# cerebellar_V1_1.net
KiCad netlist of a schematic drawn in EAGLE
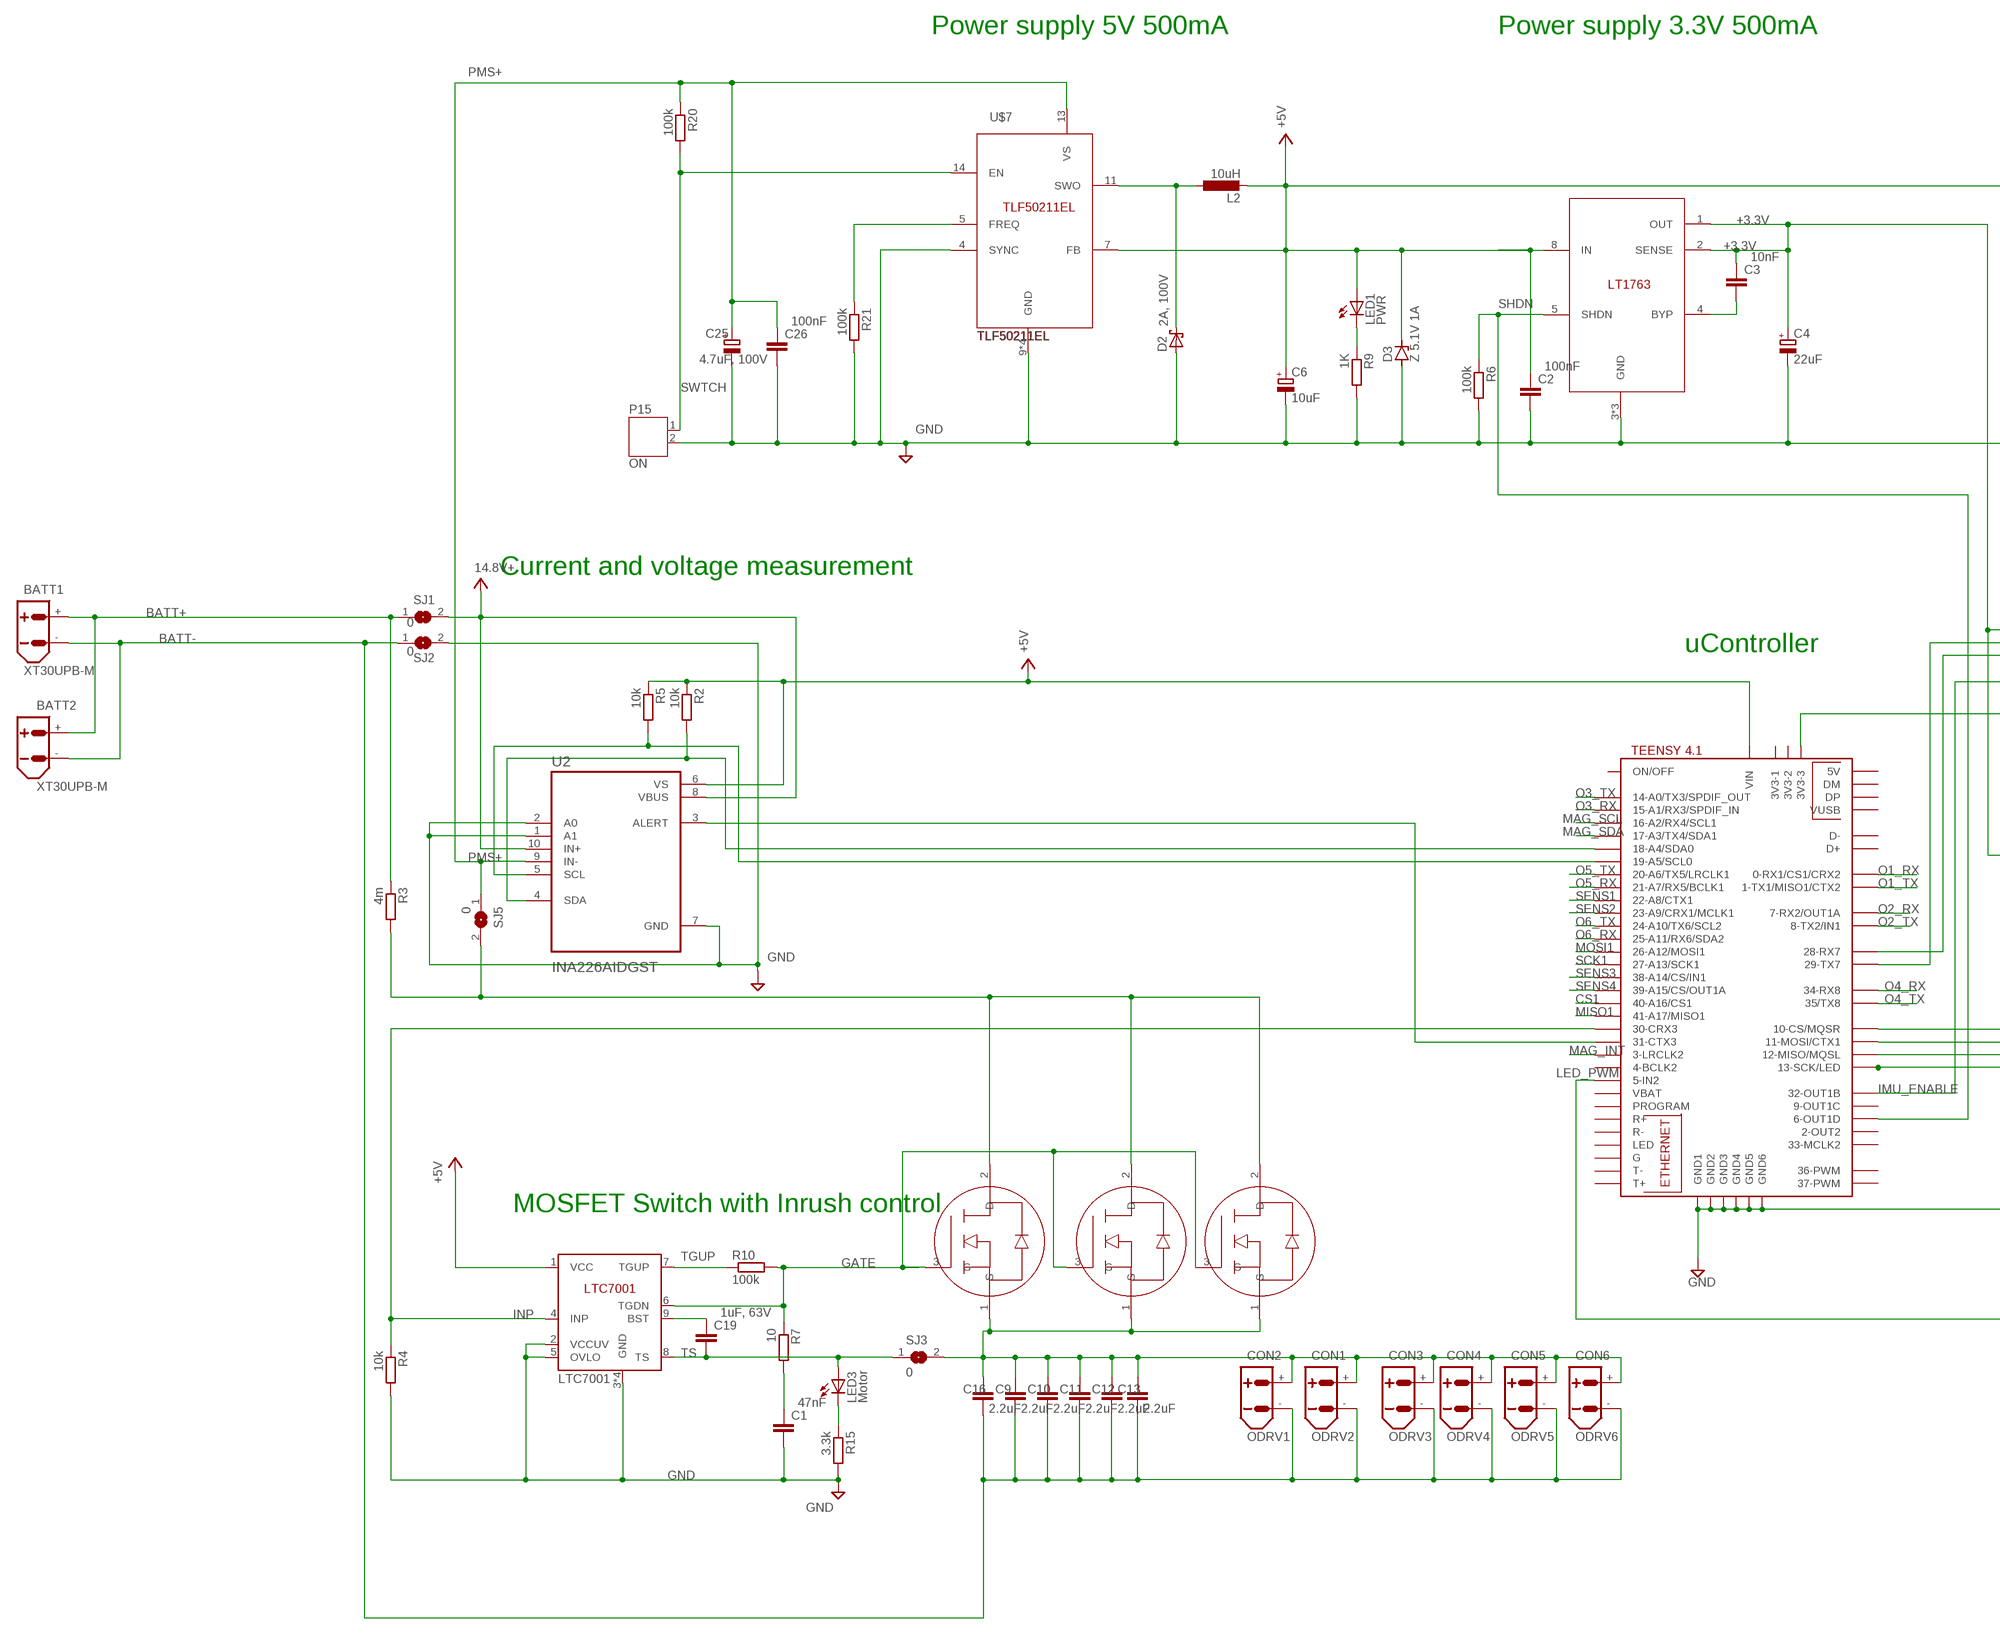
[diagram p0: schematic, sheet 1, part 1 of 2]
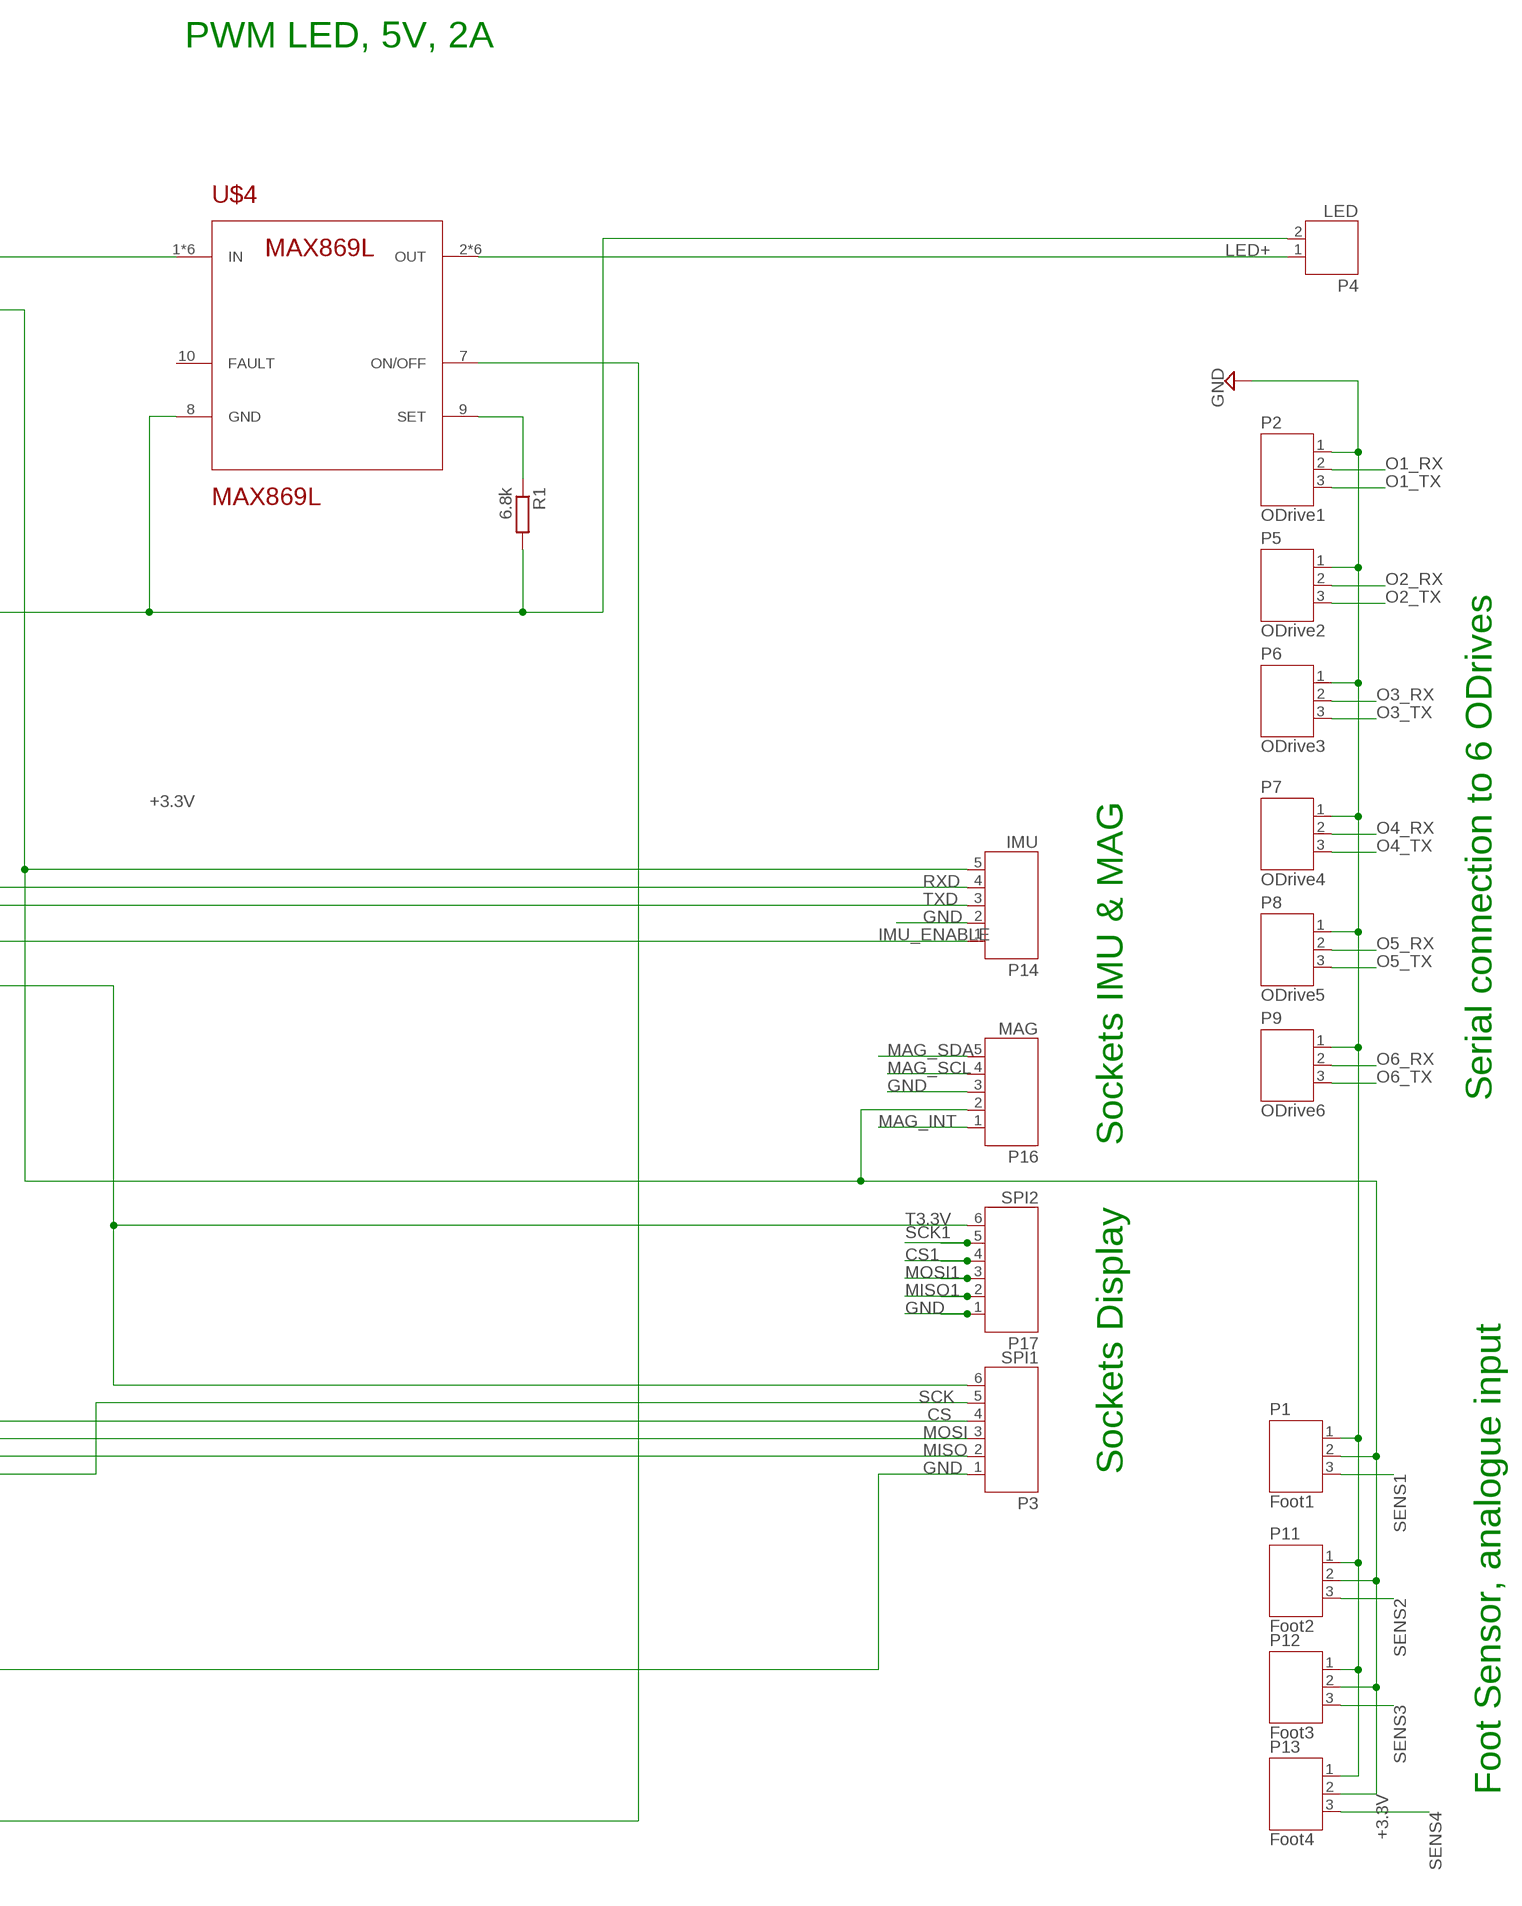
[diagram p1: schematic, sheet 1, part 2 of 2]

(export (version "E")
  (design (tool "Eeschema 10.0.6"))
  (components
    (comp (ref "BATT1")
      (value "XT30UPB-M")
      (footprint "eagle-import:XT30UPB-M")
      (libsource (lib "eagle-import") (part "XT30UPB-M"))
    )
    (comp (ref "BATT2")
      (value "XT30UPB-M")
      (footprint "eagle-import:XT30UPB-M")
      (libsource (lib "eagle-import") (part "XT30UPB-M"))
    )
    (comp (ref "C1")
      (value "47nF")
      (footprint "eagle-import:C050-024X044")
      (libsource (lib "eagle-import") (part "C-EU050-024X044"))
    )
    (comp (ref "C2")
      (value "100nF")
      (footprint "eagle-import:C050-024X044")
      (libsource (lib "eagle-import") (part "C-EU050-024X044"))
    )
    (comp (ref "C3")
      (value "10nF")
      (footprint "eagle-import:C050-024X044")
      (libsource (lib "eagle-import") (part "C-EU050-024X044"))
    )
    (comp (ref "C4")
      (value "22uF")
      (footprint "eagle-import:E2-4")
      (libsource (lib "eagle-import") (part "CPOL-EUE2-4"))
    )
    (comp (ref "C6")
      (value "10uF")
      (footprint "eagle-import:E2-4")
      (libsource (lib "eagle-import") (part "CPOL-EUE2-4"))
    )
    (comp (ref "C9")
      (value "2.2uF")
      (footprint "eagle-import:C050-024X044")
      (libsource (lib "eagle-import") (part "C-EU050-024X044"))
    )
    (comp (ref "C10")
      (value "2.2uF")
      (footprint "eagle-import:C050-024X044")
      (libsource (lib "eagle-import") (part "C-EU050-024X044"))
    )
    (comp (ref "C11")
      (value "2.2uF")
      (footprint "eagle-import:C050-024X044")
      (libsource (lib "eagle-import") (part "C-EU050-024X044"))
    )
    (comp (ref "C12")
      (value "2.2uF")
      (footprint "eagle-import:C050-024X044")
      (libsource (lib "eagle-import") (part "C-EU050-024X044"))
    )
    (comp (ref "C13")
      (value "2.2uF")
      (footprint "eagle-import:C050-024X044")
      (libsource (lib "eagle-import") (part "C-EU050-024X044"))
    )
    (comp (ref "C16")
      (value "2.2uF")
      (footprint "eagle-import:C050-024X044")
      (libsource (lib "eagle-import") (part "C-EU050-024X044"))
    )
    (comp (ref "C19")
      (value "1uF, 63V")
      (footprint "eagle-import:C050-024X044")
      (libsource (lib "eagle-import") (part "C-EU050-024X044"))
    )
    (comp (ref "C25")
      (value "4.7uF, 100V")
      (footprint "eagle-import:E2-4")
      (libsource (lib "eagle-import") (part "CPOL-EUE2-4"))
    )
    (comp (ref "C26")
      (value "100nF")
      (footprint "eagle-import:C050-024X044")
      (libsource (lib "eagle-import") (part "C-EU050-024X044"))
    )
    (comp (ref "CON1")
      (value "ODRV2")
      (footprint "eagle-import:XT30UPB-F")
      (libsource (lib "eagle-import") (part "XT30UPB-F"))
    )
    (comp (ref "CON2")
      (value "ODRV1")
      (footprint "eagle-import:XT30UPB-F")
      (libsource (lib "eagle-import") (part "XT30UPB-F"))
    )
    (comp (ref "CON3")
      (value "ODRV3")
      (footprint "eagle-import:XT30UPB-F")
      (libsource (lib "eagle-import") (part "XT30UPB-F"))
    )
    (comp (ref "CON4")
      (value "ODRV4")
      (footprint "eagle-import:XT30UPB-F")
      (libsource (lib "eagle-import") (part "XT30UPB-F"))
    )
    (comp (ref "CON5")
      (value "ODRV5")
      (footprint "eagle-import:XT30UPB-F")
      (libsource (lib "eagle-import") (part "XT30UPB-F"))
    )
    (comp (ref "CON6")
      (value "ODRV6")
      (footprint "eagle-import:XT30UPB-F")
      (libsource (lib "eagle-import") (part "XT30UPB-F"))
    )
    (comp (ref "D2")
      (value "2A, 100V")
      (footprint "eagle-import:DO41-10")
      (libsource (lib "eagle-import") (part "SCHOTTKY-DIODEDO41"))
    )
    (comp (ref "D3")
      (value "Z 5.1V 1A")
      (footprint "eagle-import:DO41Z10")
      (libsource (lib "eagle-import") (part "ZENER-DIODEDO41Z10"))
    )
    (comp (ref "IC3")
      (value "LTC7001")
      (footprint "eagle-import:MSOP10")
      (fields (field (name "MPN") "AD7992BRMZ-0"))
      (libsource (lib "eagle-import") (part "LTC7001"))
    )
    (comp (ref "L2")
      (value "10uH")
      (footprint "eagle-import:IRF-3")
      (libsource (lib "eagle-import") (part "L-EUIRF-3"))
    )
    (comp (ref "LED1")
      (value "PWR")
      (footprint "eagle-import:LED3MM")
      (libsource (lib "eagle-import") (part "LED3MM"))
    )
    (comp (ref "LED3")
      (value "Motor")
      (footprint "eagle-import:LED3MM")
      (libsource (lib "eagle-import") (part "LED3MM"))
    )
    (comp (ref "P1")
      (value "Foot1")
      (footprint "eagle-import:JST-PH3")
      (libsource (lib "eagle-import") (part "JST-PH3"))
    )
    (comp (ref "P2")
      (value "ODrive1")
      (footprint "eagle-import:JST-PH3")
      (libsource (lib "eagle-import") (part "JST-PH3"))
    )
    (comp (ref "P3")
      (value "SPI1")
      (footprint "eagle-import:JST-PH6")
      (libsource (lib "eagle-import") (part "JST-PH6"))
    )
    (comp (ref "P4")
      (value "LED")
      (footprint "eagle-import:JST-PH2")
      (libsource (lib "eagle-import") (part "JST-PH2"))
    )
    (comp (ref "P5")
      (value "ODrive2")
      (footprint "eagle-import:JST-PH3")
      (libsource (lib "eagle-import") (part "JST-PH3"))
    )
    (comp (ref "P6")
      (value "ODrive3")
      (footprint "eagle-import:JST-PH3")
      (libsource (lib "eagle-import") (part "JST-PH3"))
    )
    (comp (ref "P7")
      (value "ODrive4")
      (footprint "eagle-import:JST-PH3")
      (libsource (lib "eagle-import") (part "JST-PH3"))
    )
    (comp (ref "P8")
      (value "ODrive5")
      (footprint "eagle-import:JST-PH3")
      (libsource (lib "eagle-import") (part "JST-PH3"))
    )
    (comp (ref "P9")
      (value "ODrive6")
      (footprint "eagle-import:JST-PH3")
      (libsource (lib "eagle-import") (part "JST-PH3"))
    )
    (comp (ref "P11")
      (value "Foot2")
      (footprint "eagle-import:JST-PH3")
      (libsource (lib "eagle-import") (part "JST-PH3"))
    )
    (comp (ref "P12")
      (value "Foot3")
      (footprint "eagle-import:JST-PH3")
      (libsource (lib "eagle-import") (part "JST-PH3"))
    )
    (comp (ref "P13")
      (value "Foot4")
      (footprint "eagle-import:JST-PH3")
      (libsource (lib "eagle-import") (part "JST-PH3"))
    )
    (comp (ref "P14")
      (value "IMU")
      (footprint "eagle-import:JST-PH5")
      (libsource (lib "eagle-import") (part "JST-PH5"))
    )
    (comp (ref "P15")
      (value "ON")
      (footprint "eagle-import:JST-PH2")
      (libsource (lib "eagle-import") (part "JST-PH2"))
    )
    (comp (ref "P16")
      (value "MAG")
      (footprint "eagle-import:JST-PH5")
      (libsource (lib "eagle-import") (part "JST-PH5"))
    )
    (comp (ref "P17")
      (value "SPI2")
      (footprint "eagle-import:JST-PH6")
      (libsource (lib "eagle-import") (part "JST-PH6"))
    )
    (comp (ref "R1")
      (value "6.8k")
      (footprint "eagle-import:0204_7")
      (libsource (lib "eagle-import") (part "R-EU_0204/7"))
    )
    (comp (ref "R2")
      (value "10k")
      (footprint "eagle-import:0204_7")
      (libsource (lib "eagle-import") (part "R-EU_0204/7"))
    )
    (comp (ref "R3")
      (value "4m")
      (footprint "eagle-import:R2512")
      (libsource (lib "eagle-import") (part "R-EU_R2512"))
    )
    (comp (ref "R4")
      (value "10k")
      (footprint "eagle-import:0204_7")
      (libsource (lib "eagle-import") (part "R-EU_0204/7"))
    )
    (comp (ref "R5")
      (value "10k")
      (footprint "eagle-import:0204_7")
      (libsource (lib "eagle-import") (part "R-EU_0204/7"))
    )
    (comp (ref "R6")
      (value "100k")
      (footprint "eagle-import:0204_7")
      (libsource (lib "eagle-import") (part "R-EU_0204/7"))
    )
    (comp (ref "R7")
      (value "10")
      (footprint "eagle-import:0204_7")
      (libsource (lib "eagle-import") (part "R-EU_0204/7"))
    )
    (comp (ref "R9")
      (value "1K")
      (footprint "eagle-import:0204_7")
      (libsource (lib "eagle-import") (part "R-EU_0204/7"))
    )
    (comp (ref "R10")
      (value "100k")
      (footprint "eagle-import:0204_7")
      (libsource (lib "eagle-import") (part "R-EU_0204/7"))
    )
    (comp (ref "R15")
      (value "3.3k")
      (footprint "eagle-import:0204_7")
      (libsource (lib "eagle-import") (part "R-EU_0204/7"))
    )
    (comp (ref "R20")
      (value "100k")
      (footprint "eagle-import:0204_7")
      (libsource (lib "eagle-import") (part "R-EU_0204/7"))
    )
    (comp (ref "R21")
      (value "100k")
      (footprint "eagle-import:0204_7")
      (libsource (lib "eagle-import") (part "R-EU_0204/7"))
    )
    (comp (ref "SJ1") (value "0") (footprint "eagle-import:SJ") (libsource (lib "eagle-import") (part "SJ")))
    (comp (ref "SJ2") (value "0") (footprint "eagle-import:SJ") (libsource (lib "eagle-import") (part "SJ")))
    (comp (ref "SJ3") (value "0") (footprint "eagle-import:SJ") (libsource (lib "eagle-import") (part "SJ")))
    (comp (ref "SJ5") (value "0") (footprint "eagle-import:SJ") (libsource (lib "eagle-import") (part "SJ")))
    (comp (ref "U$1")
      (value "TEENSY41")
      (footprint "eagle-import:TEENSY41")
      (libsource (lib "eagle-import") (part "TEENSY41"))
    )
    (comp (ref "U$2")
      (value "IRF2804-BACK")
      (footprint "eagle-import:TO-220H-BACK")
      (libsource (lib "eagle-import") (part "IRF2804-BACK"))
    )
    (comp (ref "U$3")
      (value "IRF2804-BACK")
      (footprint "eagle-import:TO-220H-BACK")
      (libsource (lib "eagle-import") (part "IRF2804-BACK"))
    )
    (comp (ref "U$4")
      (value "MAX869L")
      (footprint "eagle-import:TSSOP-16")
      (libsource (lib "eagle-import") (part "MAX769L"))
    )
    (comp (ref "U$5")
      (value "IRF2804-BACK")
      (footprint "eagle-import:TO-220H-BACK")
      (libsource (lib "eagle-import") (part "IRF2804-BACK"))
    )
    (comp (ref "U$7")
      (value "TLF50211EL")
      (footprint "eagle-import:TSSOP-14")
      (libsource (lib "eagle-import") (part "TLF50211EL"))
    )
    (comp (ref "U$8")
      (value "LT1763")
      (footprint "eagle-import:SO08")
      (libsource (lib "eagle-import") (part "LT1763"))
    )
    (comp (ref "U2")
      (value "INA226AIDGST")
      (footprint "eagle-import:SOP50P490X110-10N")
      (fields (field (name "MF") "Texas Instruments"))
      (libsource (lib "eagle-import") (part "INA226AIDGST"))
    )
  )
  (nets
    (net (code "1") (name "+5V") (class "Default")
      (node (ref "C2") (pin "1") (pinfunction "1_1") (pintype "passive"))
      (node (ref "C6") (pin "+") (pinfunction "+_+") (pintype "passive"))
      (node (ref "D3") (pin "C") (pinfunction "C_C") (pintype "passive"))
      (node (ref "IC3") (pin "1") (pinfunction "VCC_1") (pintype "power_in"))
      (node (ref "L2") (pin "2") (pinfunction "2_2") (pintype "passive"))
      (node (ref "LED1") (pin "A") (pinfunction "A_A") (pintype "passive"))
      (node (ref "R2") (pin "1") (pinfunction "1_1") (pintype "passive"))
      (node (ref "R5") (pin "1") (pinfunction "1_1") (pintype "passive"))
      (node (ref "U$1") (pin "VIN") (pinfunction "VIN_VIN") (pintype "bidirectional"))
      (node (ref "U$4") (pin "1") (pinfunction "IN_1") (pintype "bidirectional"))
      (node (ref "U$4") (pin "12") (pinfunction "IN_12") (pintype "bidirectional"))
      (node (ref "U$4") (pin "13") (pinfunction "IN_13") (pintype "bidirectional"))
      (node (ref "U$4") (pin "16") (pinfunction "IN_16") (pintype "bidirectional"))
      (node (ref "U$4") (pin "4") (pinfunction "IN_4") (pintype "bidirectional"))
      (node (ref "U$4") (pin "5") (pinfunction "IN_5") (pintype "bidirectional"))
      (node (ref "U$7") (pin "7") (pinfunction "FB_7") (pintype "bidirectional"))
      (node (ref "U$8") (pin "8") (pinfunction "IN_8") (pintype "input"))
      (node (ref "U2") (pin "6") (pinfunction "VS_6") (pintype "power_in"))
    )
    (net (code "2") (name "/+3.3V") (class "Default")
      (node (ref "C3") (pin "1") (pinfunction "1_1") (pintype "passive"))
      (node (ref "C4") (pin "+") (pinfunction "+_+") (pintype "passive"))
      (node (ref "P1") (pin "2") (pinfunction "2_2") (pintype "passive"))
      (node (ref "P11") (pin "2") (pinfunction "2_2") (pintype "passive"))
      (node (ref "P12") (pin "2") (pinfunction "2_2") (pintype "passive"))
      (node (ref "P13") (pin "2") (pinfunction "2_2") (pintype "passive"))
      (node (ref "P14") (pin "5") (pinfunction "5_5") (pintype "passive"))
      (node (ref "P16") (pin "2") (pinfunction "2_2") (pintype "passive"))
      (node (ref "U$8") (pin "1") (pinfunction "OUT_1") (pintype "output"))
      (node (ref "U$8") (pin "2") (pinfunction "SENSE_2") (pintype "input"))
    )
    (net (code "3") (name "/BATT+") (class "Default")
      (node (ref "BATT1") (pin "+") (pinfunction "+_+") (pintype "power_in"))
      (node (ref "BATT2") (pin "+") (pinfunction "+_+") (pintype "power_in"))
      (node (ref "R3") (pin "1") (pinfunction "1_1") (pintype "passive"))
      (node (ref "SJ1") (pin "1") (pinfunction "1_1") (pintype "passive"))
    )
    (net (code "4") (name "/BATT-") (class "Default")
      (node (ref "BATT1") (pin "-") (pinfunction "-_-") (pintype "power_in"))
      (node (ref "BATT2") (pin "-") (pinfunction "-_-") (pintype "power_in"))
      (node (ref "C10") (pin "2") (pinfunction "2_2") (pintype "passive"))
      (node (ref "C11") (pin "2") (pinfunction "2_2") (pintype "passive"))
      (node (ref "C12") (pin "2") (pinfunction "2_2") (pintype "passive"))
      (node (ref "C13") (pin "2") (pinfunction "2_2") (pintype "passive"))
      (node (ref "C16") (pin "2") (pinfunction "2_2") (pintype "passive"))
      (node (ref "C9") (pin "2") (pinfunction "2_2") (pintype "passive"))
      (node (ref "CON1") (pin "-") (pinfunction "-_-") (pintype "power_in"))
      (node (ref "CON2") (pin "-") (pinfunction "-_-") (pintype "power_in"))
      (node (ref "CON3") (pin "-") (pinfunction "-_-") (pintype "power_in"))
      (node (ref "CON4") (pin "-") (pinfunction "-_-") (pintype "power_in"))
      (node (ref "CON5") (pin "-") (pinfunction "-_-") (pintype "power_in"))
      (node (ref "CON6") (pin "-") (pinfunction "-_-") (pintype "power_in"))
      (node (ref "SJ2") (pin "1") (pinfunction "1_1") (pintype "passive"))
    )
    (net (code "5") (name "/CS") (class "Default")
      (node (ref "P3") (pin "4") (pinfunction "4_4") (pintype "passive"))
      (node (ref "U$1") (pin "10-CS\\MQSR") (pinfunction "10-CS/MQSR_10-CS\\MQSR") (pintype "bidirectional"))
    )
    (net (code "6") (name "/CS1") (class "Default")
      (node (ref "P17") (pin "4") (pinfunction "4_4") (pintype "passive"))
      (node (ref "U$1") (pin "40-A16/CS1") (pinfunction "40-A16/CS1_40-A16/CS1") (pintype "bidirectional"))
    )
    (net (code "7") (name "/GATE") (class "Default")
      (node (ref "IC3") (pin "6") (pinfunction "TGDN_6") (pintype "output"))
      (node (ref "R10") (pin "2") (pinfunction "2_2") (pintype "passive"))
      (node (ref "R7") (pin "1") (pinfunction "1_1") (pintype "passive"))
      (node (ref "U$2") (pin "3") (pinfunction "G_3") (pintype "bidirectional"))
      (node (ref "U$3") (pin "3") (pinfunction "G_3") (pintype "bidirectional"))
      (node (ref "U$5") (pin "3") (pinfunction "G_3") (pintype "bidirectional"))
    )
    (net (code "8") (name "/IMU_ENABLE") (class "Default")
      (node (ref "P14") (pin "1") (pinfunction "1_1") (pintype "passive"))
      (node (ref "U$1") (pin "32-OUT1B") (pinfunction "32-OUT1B_32-OUT1B") (pintype "bidirectional"))
    )
    (net (code "9") (name "/INP") (class "Default")
      (node (ref "IC3") (pin "4") (pinfunction "INP_4") (pintype "input"))
      (node (ref "R4") (pin "1") (pinfunction "1_1") (pintype "passive"))
      (node (ref "U$1") (pin "30-CRX3") (pinfunction "30-CRX3_30-CRX3") (pintype "bidirectional"))
    )
    (net (code "10") (name "/LED+") (class "Default")
      (node (ref "P4") (pin "1") (pinfunction "1_1") (pintype "passive"))
      (node (ref "U$4") (pin "11") (pinfunction "OUT_11") (pintype "bidirectional"))
      (node (ref "U$4") (pin "14") (pinfunction "OUT_14") (pintype "bidirectional"))
      (node (ref "U$4") (pin "15") (pinfunction "OUT_15") (pintype "bidirectional"))
      (node (ref "U$4") (pin "2") (pinfunction "OUT_2") (pintype "bidirectional"))
      (node (ref "U$4") (pin "3") (pinfunction "OUT_3") (pintype "bidirectional"))
      (node (ref "U$4") (pin "6") (pinfunction "OUT_6") (pintype "bidirectional"))
    )
    (net (code "11") (name "/LED_PWM") (class "Default")
      (node (ref "U$1") (pin "5-IN2") (pinfunction "5-IN2_5-IN2") (pintype "bidirectional"))
      (node (ref "U$4") (pin "7") (pinfunction "ON/OFF_7") (pintype "bidirectional"))
    )
    (net (code "12") (name "/MAG_INT") (class "Default")
      (node (ref "P16") (pin "1") (pinfunction "1_1") (pintype "passive"))
      (node (ref "U$1") (pin "3-LRCLK2") (pinfunction "3-LRCLK2_3-LRCLK2") (pintype "bidirectional"))
    )
    (net (code "13") (name "/MAG_SCL") (class "Default")
      (node (ref "P16") (pin "4") (pinfunction "4_4") (pintype "passive"))
      (node (ref "U$1") (pin "16-A2/RX4/SCL1") (pinfunction "16-A2/RX4/SCL1_16-A2/RX4/SCL1") (pintype "bidirectional"))
    )
    (net (code "14") (name "/MAG_SDA") (class "Default")
      (node (ref "P16") (pin "5") (pinfunction "5_5") (pintype "passive"))
      (node (ref "U$1") (pin "17-A3/TX4/SDA1") (pinfunction "17-A3/TX4/SDA1_17-A3/TX4/SDA1") (pintype "bidirectional"))
    )
    (net (code "15") (name "/MISO") (class "Default")
      (node (ref "P3") (pin "2") (pinfunction "2_2") (pintype "passive"))
      (node (ref "U$1") (pin "12-MISO/MQSL") (pinfunction "12-MISO/MQSL_12-MISO/MQSL") (pintype "bidirectional"))
    )
    (net (code "16") (name "/MISO1") (class "Default")
      (node (ref "P17") (pin "2") (pinfunction "2_2") (pintype "passive"))
      (node (ref "U$1") (pin "41-A17/MISO1") (pinfunction "41-A17/MISO1_41-A17/MISO1") (pintype "bidirectional"))
    )
    (net (code "17") (name "/MOSI") (class "Default")
      (node (ref "P3") (pin "3") (pinfunction "3_3") (pintype "passive"))
      (node (ref "U$1") (pin "11-MOSI/CTX1") (pinfunction "11-MOSI/CTX1_11-MOSI/CTX1") (pintype "bidirectional"))
    )
    (net (code "18") (name "/MOSI1") (class "Default")
      (node (ref "P17") (pin "3") (pinfunction "3_3") (pintype "passive"))
      (node (ref "U$1") (pin "26-A12/MOSI1") (pinfunction "26-A12/MOSI1_26-A12/MOSI1") (pintype "bidirectional"))
    )
    (net (code "19") (name "/O1_RX") (class "Default")
      (node (ref "P2") (pin "2") (pinfunction "2_2") (pintype "passive"))
      (node (ref "U$1") (pin "0-RX1/CS1/CRX2") (pinfunction "0-RX1/CS1/CRX2_0-RX1/CS1/CRX2") (pintype "bidirectional"))
    )
    (net (code "20") (name "/O1_TX") (class "Default")
      (node (ref "P2") (pin "3") (pinfunction "3_3") (pintype "passive"))
      (node (ref "U$1") (pin "1-TX1/MISO1/CTX2") (pinfunction "1-TX1/MISO1/CTX2_1-TX1/MISO1/CTX2") (pintype "bidirectional"))
    )
    (net (code "21") (name "/O2_RX") (class "Default")
      (node (ref "P5") (pin "2") (pinfunction "2_2") (pintype "passive"))
      (node (ref "U$1") (pin "7-RX2/OUT1A") (pinfunction "7-RX2/OUT1A_7-RX2/OUT1A") (pintype "bidirectional"))
    )
    (net (code "22") (name "/O2_TX") (class "Default")
      (node (ref "P5") (pin "3") (pinfunction "3_3") (pintype "passive"))
      (node (ref "U$1") (pin "8-TX2/IN1") (pinfunction "8-TX2/IN1_8-TX2/IN1") (pintype "bidirectional"))
    )
    (net (code "23") (name "/O3_RX") (class "Default")
      (node (ref "P6") (pin "2") (pinfunction "2_2") (pintype "passive"))
      (node (ref "U$1") (pin "15-A1/RX3/SPDIF_IN") (pinfunction "15-A1/RX3/SPDIF_IN_15-A1/RX3/SPDIF_IN") (pintype "bidirectional"))
    )
    (net (code "24") (name "/O3_TX") (class "Default")
      (node (ref "P6") (pin "3") (pinfunction "3_3") (pintype "passive"))
      (node (ref "U$1") (pin "14-A0/TX3/SPDIF_OUT") (pinfunction "14-A0/TX3/SPDIF_OUT_14-A0/TX3/SPDIF_OUT") (pintype "bidirectional"))
    )
    (net (code "25") (name "/O4_RX") (class "Default")
      (node (ref "P7") (pin "2") (pinfunction "2_2") (pintype "passive"))
      (node (ref "U$1") (pin "34-RX8") (pinfunction "34-RX8_34-RX8") (pintype "bidirectional"))
    )
    (net (code "26") (name "/O4_TX") (class "Default")
      (node (ref "P7") (pin "3") (pinfunction "3_3") (pintype "passive"))
      (node (ref "U$1") (pin "35-TX8") (pinfunction "35/TX8_35-TX8") (pintype "bidirectional"))
    )
    (net (code "27") (name "/O5_RX") (class "Default")
      (node (ref "P8") (pin "2") (pinfunction "2_2") (pintype "passive"))
      (node (ref "U$1") (pin "21-A7/RX5/BCLK1") (pinfunction "21-A7/RX5/BCLK1_21-A7/RX5/BCLK1") (pintype "bidirectional"))
    )
    (net (code "28") (name "/O5_TX") (class "Default")
      (node (ref "P8") (pin "3") (pinfunction "3_3") (pintype "passive"))
      (node (ref "U$1") (pin "20-A6/TX5/LRCLK1") (pinfunction "20-A6/TX5/LRCLK1_20-A6/TX5/LRCLK1") (pintype "bidirectional"))
    )
    (net (code "29") (name "/O6_RX") (class "Default")
      (node (ref "P9") (pin "2") (pinfunction "2_2") (pintype "passive"))
      (node (ref "U$1") (pin "25-A11/RX6/SDA2") (pinfunction "25-A11/RX6/SDA2_25-A11/RX6/SDA2") (pintype "bidirectional"))
    )
    (net (code "30") (name "/O6_TX") (class "Default")
      (node (ref "P9") (pin "3") (pinfunction "3_3") (pintype "passive"))
      (node (ref "U$1") (pin "24-A10/TX6/SCL2") (pinfunction "24-A10/TX6/SCL2_24-A10/TX6/SCL2") (pintype "bidirectional"))
    )
    (net (code "31") (name "/PMS+") (class "Default")
      (node (ref "C25") (pin "+") (pinfunction "+_+") (pintype "passive"))
      (node (ref "C26") (pin "1") (pinfunction "1_1") (pintype "passive"))
      (node (ref "R20") (pin "1") (pinfunction "1_1") (pintype "passive"))
      (node (ref "SJ5") (pin "1") (pinfunction "1_1") (pintype "passive"))
      (node (ref "U$7") (pin "13") (pinfunction "VS_13") (pintype "bidirectional"))
      (node (ref "U2") (pin "9") (pinfunction "IN-_9") (pintype "input"))
    )
    (net (code "32") (name "/RXD") (class "Default")
      (node (ref "P14") (pin "4") (pinfunction "4_4") (pintype "passive"))
      (node (ref "U$1") (pin "29-TX7") (pinfunction "29-TX7_29-TX7") (pintype "bidirectional"))
    )
    (net (code "33") (name "/SCK") (class "Default")
      (node (ref "P3") (pin "5") (pinfunction "5_5") (pintype "passive"))
      (node (ref "U$1") (pin "13-SCK/LED") (pinfunction "13-SCK/LED_13-SCK/LED") (pintype "bidirectional"))
    )
    (net (code "34") (name "/SCK1") (class "Default")
      (node (ref "P17") (pin "5") (pinfunction "5_5") (pintype "passive"))
      (node (ref "U$1") (pin "27-A13/SCK1") (pinfunction "27-A13/SCK1_27-A13/SCK1") (pintype "bidirectional"))
    )
    (net (code "35") (name "/SENS1") (class "Default")
      (node (ref "P1") (pin "3") (pinfunction "3_3") (pintype "passive"))
      (node (ref "U$1") (pin "22-A8/CTX1") (pinfunction "22-A8/CTX1_22-A8/CTX1") (pintype "bidirectional"))
    )
    (net (code "36") (name "/SENS2") (class "Default")
      (node (ref "P11") (pin "3") (pinfunction "3_3") (pintype "passive"))
      (node (ref "U$1") (pin "23-A9/CRX1/MCLK1") (pinfunction "23-A9/CRX1/MCLK1_23-A9/CRX1/MCLK1") (pintype "bidirectional"))
    )
    (net (code "37") (name "/SENS3") (class "Default")
      (node (ref "P12") (pin "3") (pinfunction "3_3") (pintype "passive"))
      (node (ref "U$1") (pin "38-A14/CS/IN1") (pinfunction "38-A14/CS/IN1_38-A14/CS/IN1") (pintype "bidirectional"))
    )
    (net (code "38") (name "/SENS4") (class "Default")
      (node (ref "P13") (pin "3") (pinfunction "3_3") (pintype "passive"))
      (node (ref "U$1") (pin "39-A15/CS/OUT1A") (pinfunction "39-A15/CS/OUT1A_39-A15/CS/OUT1A") (pintype "bidirectional"))
    )
    (net (code "39") (name "/SHDN") (class "Default")
      (node (ref "R6") (pin "1") (pinfunction "1_1") (pintype "passive"))
      (node (ref "U$1") (pin "6-OUT1D") (pinfunction "6-OUT1D_6-OUT1D") (pintype "bidirectional"))
      (node (ref "U$8") (pin "5") (pinfunction "SHDN_5") (pintype "bidirectional"))
    )
    (net (code "40") (name "/SWTCH") (class "Default")
      (node (ref "P15") (pin "1") (pinfunction "1_1") (pintype "passive"))
      (node (ref "R20") (pin "2") (pinfunction "2_2") (pintype "passive"))
      (node (ref "U$7") (pin "14") (pinfunction "EN_14") (pintype "bidirectional"))
    )
    (net (code "41") (name "/T3.3V") (class "Default")
      (node (ref "P17") (pin "6") (pinfunction "6_6") (pintype "passive"))
      (node (ref "P3") (pin "6") (pinfunction "6_6") (pintype "passive"))
      (node (ref "U$1") (pin "3V3-3") (pinfunction "3V3-3_3V3-3") (pintype "bidirectional"))
    )
    (net (code "42") (name "/TGUP") (class "Default")
      (node (ref "IC3") (pin "7") (pinfunction "TGUP_7") (pintype "input"))
      (node (ref "R10") (pin "1") (pinfunction "1_1") (pintype "passive"))
    )
    (net (code "43") (name "/TS") (class "Default")
      (node (ref "C19") (pin "2") (pinfunction "2_2") (pintype "passive"))
      (node (ref "IC3") (pin "8") (pinfunction "TS_8") (pintype "bidirectional"))
      (node (ref "LED3") (pin "A") (pinfunction "A_A") (pintype "passive"))
      (node (ref "SJ3") (pin "1") (pinfunction "1_1") (pintype "passive"))
    )
    (net (code "44") (name "/TXD") (class "Default")
      (node (ref "P14") (pin "3") (pinfunction "3_3") (pintype "passive"))
      (node (ref "U$1") (pin "28-RX7") (pinfunction "28-RX7_28-RX7") (pintype "bidirectional"))
    )
    (net (code "45") (name "14.8V+") (class "Default")
      (node (ref "SJ1") (pin "2") (pinfunction "2_2") (pintype "passive"))
      (node (ref "U2") (pin "10") (pinfunction "IN+_10") (pintype "input"))
      (node (ref "U2") (pin "8") (pinfunction "VBUS_8") (pintype "power_in"))
    )
    (net (code "46") (name "GND") (class "Default")
      (node (ref "C1") (pin "2") (pinfunction "2_2") (pintype "passive"))
      (node (ref "C2") (pin "2") (pinfunction "2_2") (pintype "passive"))
      (node (ref "C25") (pin "-") (pinfunction "-_-") (pintype "passive"))
      (node (ref "C26") (pin "2") (pinfunction "2_2") (pintype "passive"))
      (node (ref "C4") (pin "-") (pinfunction "-_-") (pintype "passive"))
      (node (ref "C6") (pin "-") (pinfunction "-_-") (pintype "passive"))
      (node (ref "D2") (pin "A") (pinfunction "A_A") (pintype "passive"))
      (node (ref "D3") (pin "A") (pinfunction "A_A") (pintype "passive"))
      (node (ref "IC3") (pin "10") (pinfunction "GND_10") (pintype "power_in"))
      (node (ref "IC3") (pin "11") (pinfunction "GND_11") (pintype "power_in"))
      (node (ref "IC3") (pin "12") (pinfunction "GND_12") (pintype "power_in"))
      (node (ref "IC3") (pin "2") (pinfunction "VCCUV_2") (pintype "input"))
      (node (ref "IC3") (pin "3") (pinfunction "GND_3") (pintype "power_in"))
      (node (ref "IC3") (pin "5") (pinfunction "OVLO_5") (pintype "input"))
      (node (ref "P1") (pin "1") (pinfunction "1_1") (pintype "passive"))
      (node (ref "P11") (pin "1") (pinfunction "1_1") (pintype "passive"))
      (node (ref "P12") (pin "1") (pinfunction "1_1") (pintype "passive"))
      (node (ref "P13") (pin "1") (pinfunction "1_1") (pintype "passive"))
      (node (ref "P14") (pin "2") (pinfunction "2_2") (pintype "passive"))
      (node (ref "P15") (pin "2") (pinfunction "2_2") (pintype "passive"))
      (node (ref "P16") (pin "3") (pinfunction "3_3") (pintype "passive"))
      (node (ref "P17") (pin "1") (pinfunction "1_1") (pintype "passive"))
      (node (ref "P2") (pin "1") (pinfunction "1_1") (pintype "passive"))
      (node (ref "P3") (pin "1") (pinfunction "1_1") (pintype "passive"))
      (node (ref "P4") (pin "2") (pinfunction "2_2") (pintype "passive"))
      (node (ref "P5") (pin "1") (pinfunction "1_1") (pintype "passive"))
      (node (ref "P6") (pin "1") (pinfunction "1_1") (pintype "passive"))
      (node (ref "P7") (pin "1") (pinfunction "1_1") (pintype "passive"))
      (node (ref "P8") (pin "1") (pinfunction "1_1") (pintype "passive"))
      (node (ref "P9") (pin "1") (pinfunction "1_1") (pintype "passive"))
      (node (ref "R1") (pin "2") (pinfunction "2_2") (pintype "passive"))
      (node (ref "R15") (pin "2") (pinfunction "2_2") (pintype "passive"))
      (node (ref "R21") (pin "2") (pinfunction "2_2") (pintype "passive"))
      (node (ref "R4") (pin "2") (pinfunction "2_2") (pintype "passive"))
      (node (ref "R6") (pin "2") (pinfunction "2_2") (pintype "passive"))
      (node (ref "R9") (pin "2") (pinfunction "2_2") (pintype "passive"))
      (node (ref "SJ2") (pin "2") (pinfunction "2_2") (pintype "passive"))
      (node (ref "U$1") (pin "GND1") (pinfunction "GND1_GND1") (pintype "bidirectional"))
      (node (ref "U$1") (pin "GND2") (pinfunction "GND2_GND2") (pintype "bidirectional"))
      (node (ref "U$1") (pin "GND3") (pinfunction "GND3_GND3") (pintype "bidirectional"))
      (node (ref "U$1") (pin "GND4") (pinfunction "GND4_GND4") (pintype "bidirectional"))
      (node (ref "U$1") (pin "GND5") (pinfunction "GND5_GND5") (pintype "bidirectional"))
      (node (ref "U$1") (pin "GND6") (pinfunction "GND6_GND6") (pintype "bidirectional"))
      (node (ref "U$4") (pin "8") (pinfunction "GND_8") (pintype "bidirectional"))
      (node (ref "U$7") (pin "10") (pinfunction "GND_10") (pintype "bidirectional"))
      (node (ref "U$7") (pin "15") (pinfunction "GND_15") (pintype "bidirectional"))
      (node (ref "U$7") (pin "16") (pinfunction "GND_16") (pintype "bidirectional"))
      (node (ref "U$7") (pin "4") (pinfunction "SYNC_4") (pintype "bidirectional"))
      (node (ref "U$7") (pin "9") (pinfunction "GND_9") (pintype "bidirectional"))
      (node (ref "U$8") (pin "3") (pinfunction "GND_3") (pintype "bidirectional"))
      (node (ref "U$8") (pin "6") (pinfunction "GND_6") (pintype "bidirectional"))
      (node (ref "U$8") (pin "7") (pinfunction "GND_7") (pintype "bidirectional"))
      (node (ref "U2") (pin "1") (pinfunction "A1_1") (pintype "input"))
      (node (ref "U2") (pin "2") (pinfunction "A0_2") (pintype "input"))
      (node (ref "U2") (pin "7") (pinfunction "GND_7") (pintype "power_in"))
    )
    (net (code "47") (name "Net-(C1-Pad1)") (class "Default")
      (node (ref "C1") (pin "1") (pinfunction "1_1") (pintype "passive"))
      (node (ref "R7") (pin "2") (pinfunction "2_2") (pintype "passive"))
    )
    (net (code "48") (name "Net-(IC3-BST)") (class "Default")
      (node (ref "C19") (pin "1") (pinfunction "1_1") (pintype "passive"))
      (node (ref "IC3") (pin "9") (pinfunction "BST_9") (pintype "input"))
    )
    (net (code "49") (name "Net-(LED1-C)") (class "Default")
      (node (ref "LED1") (pin "K") (pinfunction "C_K") (pintype "passive"))
      (node (ref "R9") (pin "1") (pinfunction "1_1") (pintype "passive"))
    )
    (net (code "50") (name "Net-(LED3-C)") (class "Default")
      (node (ref "LED3") (pin "K") (pinfunction "C_K") (pintype "passive"))
      (node (ref "R15") (pin "1") (pinfunction "1_1") (pintype "passive"))
    )
    (net (code "51") (name "Net-(U$2-D)") (class "Default")
      (node (ref "R3") (pin "2") (pinfunction "2_2") (pintype "passive"))
      (node (ref "SJ5") (pin "2") (pinfunction "2_2") (pintype "passive"))
      (node (ref "U$2") (pin "2") (pinfunction "D_2") (pintype "bidirectional"))
      (node (ref "U$3") (pin "2") (pinfunction "D_2") (pintype "bidirectional"))
      (node (ref "U$5") (pin "2") (pinfunction "D_2") (pintype "bidirectional"))
    )
    (net (code "52") (name "Net-(U$2-S)") (class "Default")
      (node (ref "C10") (pin "1") (pinfunction "1_1") (pintype "passive"))
      (node (ref "C11") (pin "1") (pinfunction "1_1") (pintype "passive"))
      (node (ref "C12") (pin "1") (pinfunction "1_1") (pintype "passive"))
      (node (ref "C13") (pin "1") (pinfunction "1_1") (pintype "passive"))
      (node (ref "C16") (pin "1") (pinfunction "1_1") (pintype "passive"))
      (node (ref "C9") (pin "1") (pinfunction "1_1") (pintype "passive"))
      (node (ref "CON1") (pin "+") (pinfunction "+_+") (pintype "power_in"))
      (node (ref "CON2") (pin "+") (pinfunction "+_+") (pintype "power_in"))
      (node (ref "CON3") (pin "+") (pinfunction "+_+") (pintype "power_in"))
      (node (ref "CON4") (pin "+") (pinfunction "+_+") (pintype "power_in"))
      (node (ref "CON5") (pin "+") (pinfunction "+_+") (pintype "power_in"))
      (node (ref "CON6") (pin "+") (pinfunction "+_+") (pintype "power_in"))
      (node (ref "SJ3") (pin "2") (pinfunction "2_2") (pintype "passive"))
      (node (ref "U$2") (pin "1") (pinfunction "S_1") (pintype "bidirectional"))
      (node (ref "U$3") (pin "1") (pinfunction "S_1") (pintype "bidirectional"))
      (node (ref "U$5") (pin "1") (pinfunction "S_1") (pintype "bidirectional"))
    )
    (net (code "53") (name "Net-(U$4-SET)") (class "Default")
      (node (ref "R1") (pin "1") (pinfunction "1_1") (pintype "passive"))
      (node (ref "U$4") (pin "9") (pinfunction "SET_9") (pintype "bidirectional"))
    )
    (net (code "54") (name "Net-(U$7-FREQ)") (class "Default")
      (node (ref "R21") (pin "1") (pinfunction "1_1") (pintype "passive"))
      (node (ref "U$7") (pin "5") (pinfunction "FREQ_5") (pintype "bidirectional"))
    )
    (net (code "55") (name "Net-(U$7-SWO)") (class "Default")
      (node (ref "D2") (pin "C") (pinfunction "C_C") (pintype "passive"))
      (node (ref "L2") (pin "1") (pinfunction "1_1") (pintype "passive"))
      (node (ref "U$7") (pin "11") (pinfunction "SWO_11") (pintype "bidirectional"))
    )
    (net (code "56") (name "Net-(U$8-BYP)") (class "Default")
      (node (ref "C3") (pin "2") (pinfunction "2_2") (pintype "passive"))
      (node (ref "U$8") (pin "4") (pinfunction "BYP_4") (pintype "bidirectional"))
    )
    (net (code "57") (name "Net-(U2-ALERT)") (class "Default")
      (node (ref "U$1") (pin "31-CTX3") (pinfunction "31-CTX3_31-CTX3") (pintype "bidirectional"))
      (node (ref "U2") (pin "3") (pinfunction "ALERT_3") (pintype "output"))
    )
    (net (code "58") (name "Net-(U2-SCL)") (class "Default")
      (node (ref "R5") (pin "2") (pinfunction "2_2") (pintype "passive"))
      (node (ref "U$1") (pin "19-A5/SCL0") (pinfunction "19-A5/SCL0_19-A5/SCL0") (pintype "bidirectional"))
      (node (ref "U2") (pin "5") (pinfunction "SCL_5") (pintype "input"))
    )
    (net (code "59") (name "Net-(U2-SDA)") (class "Default")
      (node (ref "R2") (pin "2") (pinfunction "2_2") (pintype "passive"))
      (node (ref "U$1") (pin "18-A4/SDA0") (pinfunction "18-A4/SDA0_18-A4/SDA0") (pintype "bidirectional"))
      (node (ref "U2") (pin "4") (pinfunction "SDA_4") (pintype "bidirectional"))
    )
    (net (code "60") (name "unconnected-(U$1-5V-Pad+5V)") (class "Default")
      (node (ref "U$1") (pin "+5V") (pinfunction "5V_+5V") (pintype "bidirectional"))
    )
    (net (code "61") (name "unconnected-(U$1-Pad2-OUT2)") (class "Default")
      (node (ref "U$1") (pin "2-OUT2") (pinfunction "2-OUT2_2-OUT2") (pintype "bidirectional"))
    )
    (net (code "62") (name "unconnected-(U$1-Pad3V3-1)") (class "Default")
      (node (ref "U$1") (pin "3V3-1") (pinfunction "3V3-1_3V3-1") (pintype "bidirectional"))
    )
    (net (code "63") (name "unconnected-(U$1-Pad3V3-2)") (class "Default")
      (node (ref "U$1") (pin "3V3-2") (pinfunction "3V3-2_3V3-2") (pintype "bidirectional"))
    )
    (net (code "64") (name "unconnected-(U$1-Pad4-BCLK2)") (class "Default")
      (node (ref "U$1") (pin "4-BCLK2") (pinfunction "4-BCLK2_4-BCLK2") (pintype "bidirectional"))
    )
    (net (code "65") (name "unconnected-(U$1-Pad9-OUT1C)") (class "Default")
      (node (ref "U$1") (pin "9-OUT1C") (pinfunction "9-OUT1C_9-OUT1C") (pintype "bidirectional"))
    )
    (net (code "66") (name "unconnected-(U$1-Pad33-MCLK2)") (class "Default")
      (node (ref "U$1") (pin "33-MCLK2") (pinfunction "33-MCLK2_33-MCLK2") (pintype "bidirectional"))
    )
    (net (code "67") (name "unconnected-(U$1-Pad36-PWM)") (class "Default")
      (node (ref "U$1") (pin "36-PWM") (pinfunction "36-PWM_36-PWM") (pintype "bidirectional"))
    )
    (net (code "68") (name "unconnected-(U$1-Pad37-PWM)") (class "Default")
      (node (ref "U$1") (pin "37-PWM") (pinfunction "37-PWM_37-PWM") (pintype "bidirectional"))
    )
    (net (code "69") (name "unconnected-(U$1-PadD+)") (class "Default")
      (node (ref "U$1") (pin "D+") (pinfunction "D+_D+") (pintype "bidirectional"))
    )
    (net (code "70") (name "unconnected-(U$1-PadD-)") (class "Default")
      (node (ref "U$1") (pin "D-") (pinfunction "D-_D-") (pintype "bidirectional"))
    )
    (net (code "71") (name "unconnected-(U$1-PadDM)") (class "Default")
      (node (ref "U$1") (pin "DM") (pinfunction "DM_DM") (pintype "bidirectional"))
    )
    (net (code "72") (name "unconnected-(U$1-PadDP)") (class "Default")
      (node (ref "U$1") (pin "DP") (pinfunction "DP_DP") (pintype "bidirectional"))
    )
    (net (code "73") (name "unconnected-(U$1-PadG)") (class "Default")
      (node (ref "U$1") (pin "G") (pinfunction "G_G") (pintype "bidirectional"))
    )
    (net (code "74") (name "unconnected-(U$1-PadLED)") (class "Default")
      (node (ref "U$1") (pin "LED") (pinfunction "LED_LED") (pintype "bidirectional"))
    )
    (net (code "75") (name "unconnected-(U$1-PadON{slash}OFF)") (class "Default")
      (node (ref "U$1") (pin "ON/OFF") (pinfunction "ON/OFF_ON/OFF") (pintype "bidirectional"))
    )
    (net (code "76") (name "unconnected-(U$1-PadPROGRAM)") (class "Default")
      (node (ref "U$1") (pin "PROGRAM") (pinfunction "PROGRAM_PROGRAM") (pintype "bidirectional"))
    )
    (net (code "77") (name "unconnected-(U$1-PadR+)") (class "Default")
      (node (ref "U$1") (pin "R+") (pinfunction "R+_R+") (pintype "bidirectional"))
    )
    (net (code "78") (name "unconnected-(U$1-PadR-)") (class "Default")
      (node (ref "U$1") (pin "R-") (pinfunction "R-_R-") (pintype "bidirectional"))
    )
    (net (code "79") (name "unconnected-(U$1-PadT+)") (class "Default")
      (node (ref "U$1") (pin "T+") (pinfunction "T+_T+") (pintype "bidirectional"))
    )
    (net (code "80") (name "unconnected-(U$1-PadT-)") (class "Default")
      (node (ref "U$1") (pin "T-") (pinfunction "T-_T-") (pintype "bidirectional"))
    )
    (net (code "81") (name "unconnected-(U$1-PadVBAT)") (class "Default")
      (node (ref "U$1") (pin "VBAT") (pinfunction "VBAT_VBAT") (pintype "bidirectional"))
    )
    (net (code "82") (name "unconnected-(U$1-PadVUSB)") (class "Default")
      (node (ref "U$1") (pin "VUSB") (pinfunction "VUSB_VUSB") (pintype "bidirectional"))
    )
    (net (code "83") (name "unconnected-(U$4-FAULT-Pad10)") (class "Default")
      (node (ref "U$4") (pin "10") (pinfunction "FAULT_10") (pintype "bidirectional"))
    )
  )
)
